# SCH_NFC-Hacker-Card_2024-08-06.net
KiCad netlist of a schematic drawn in EasyEDA
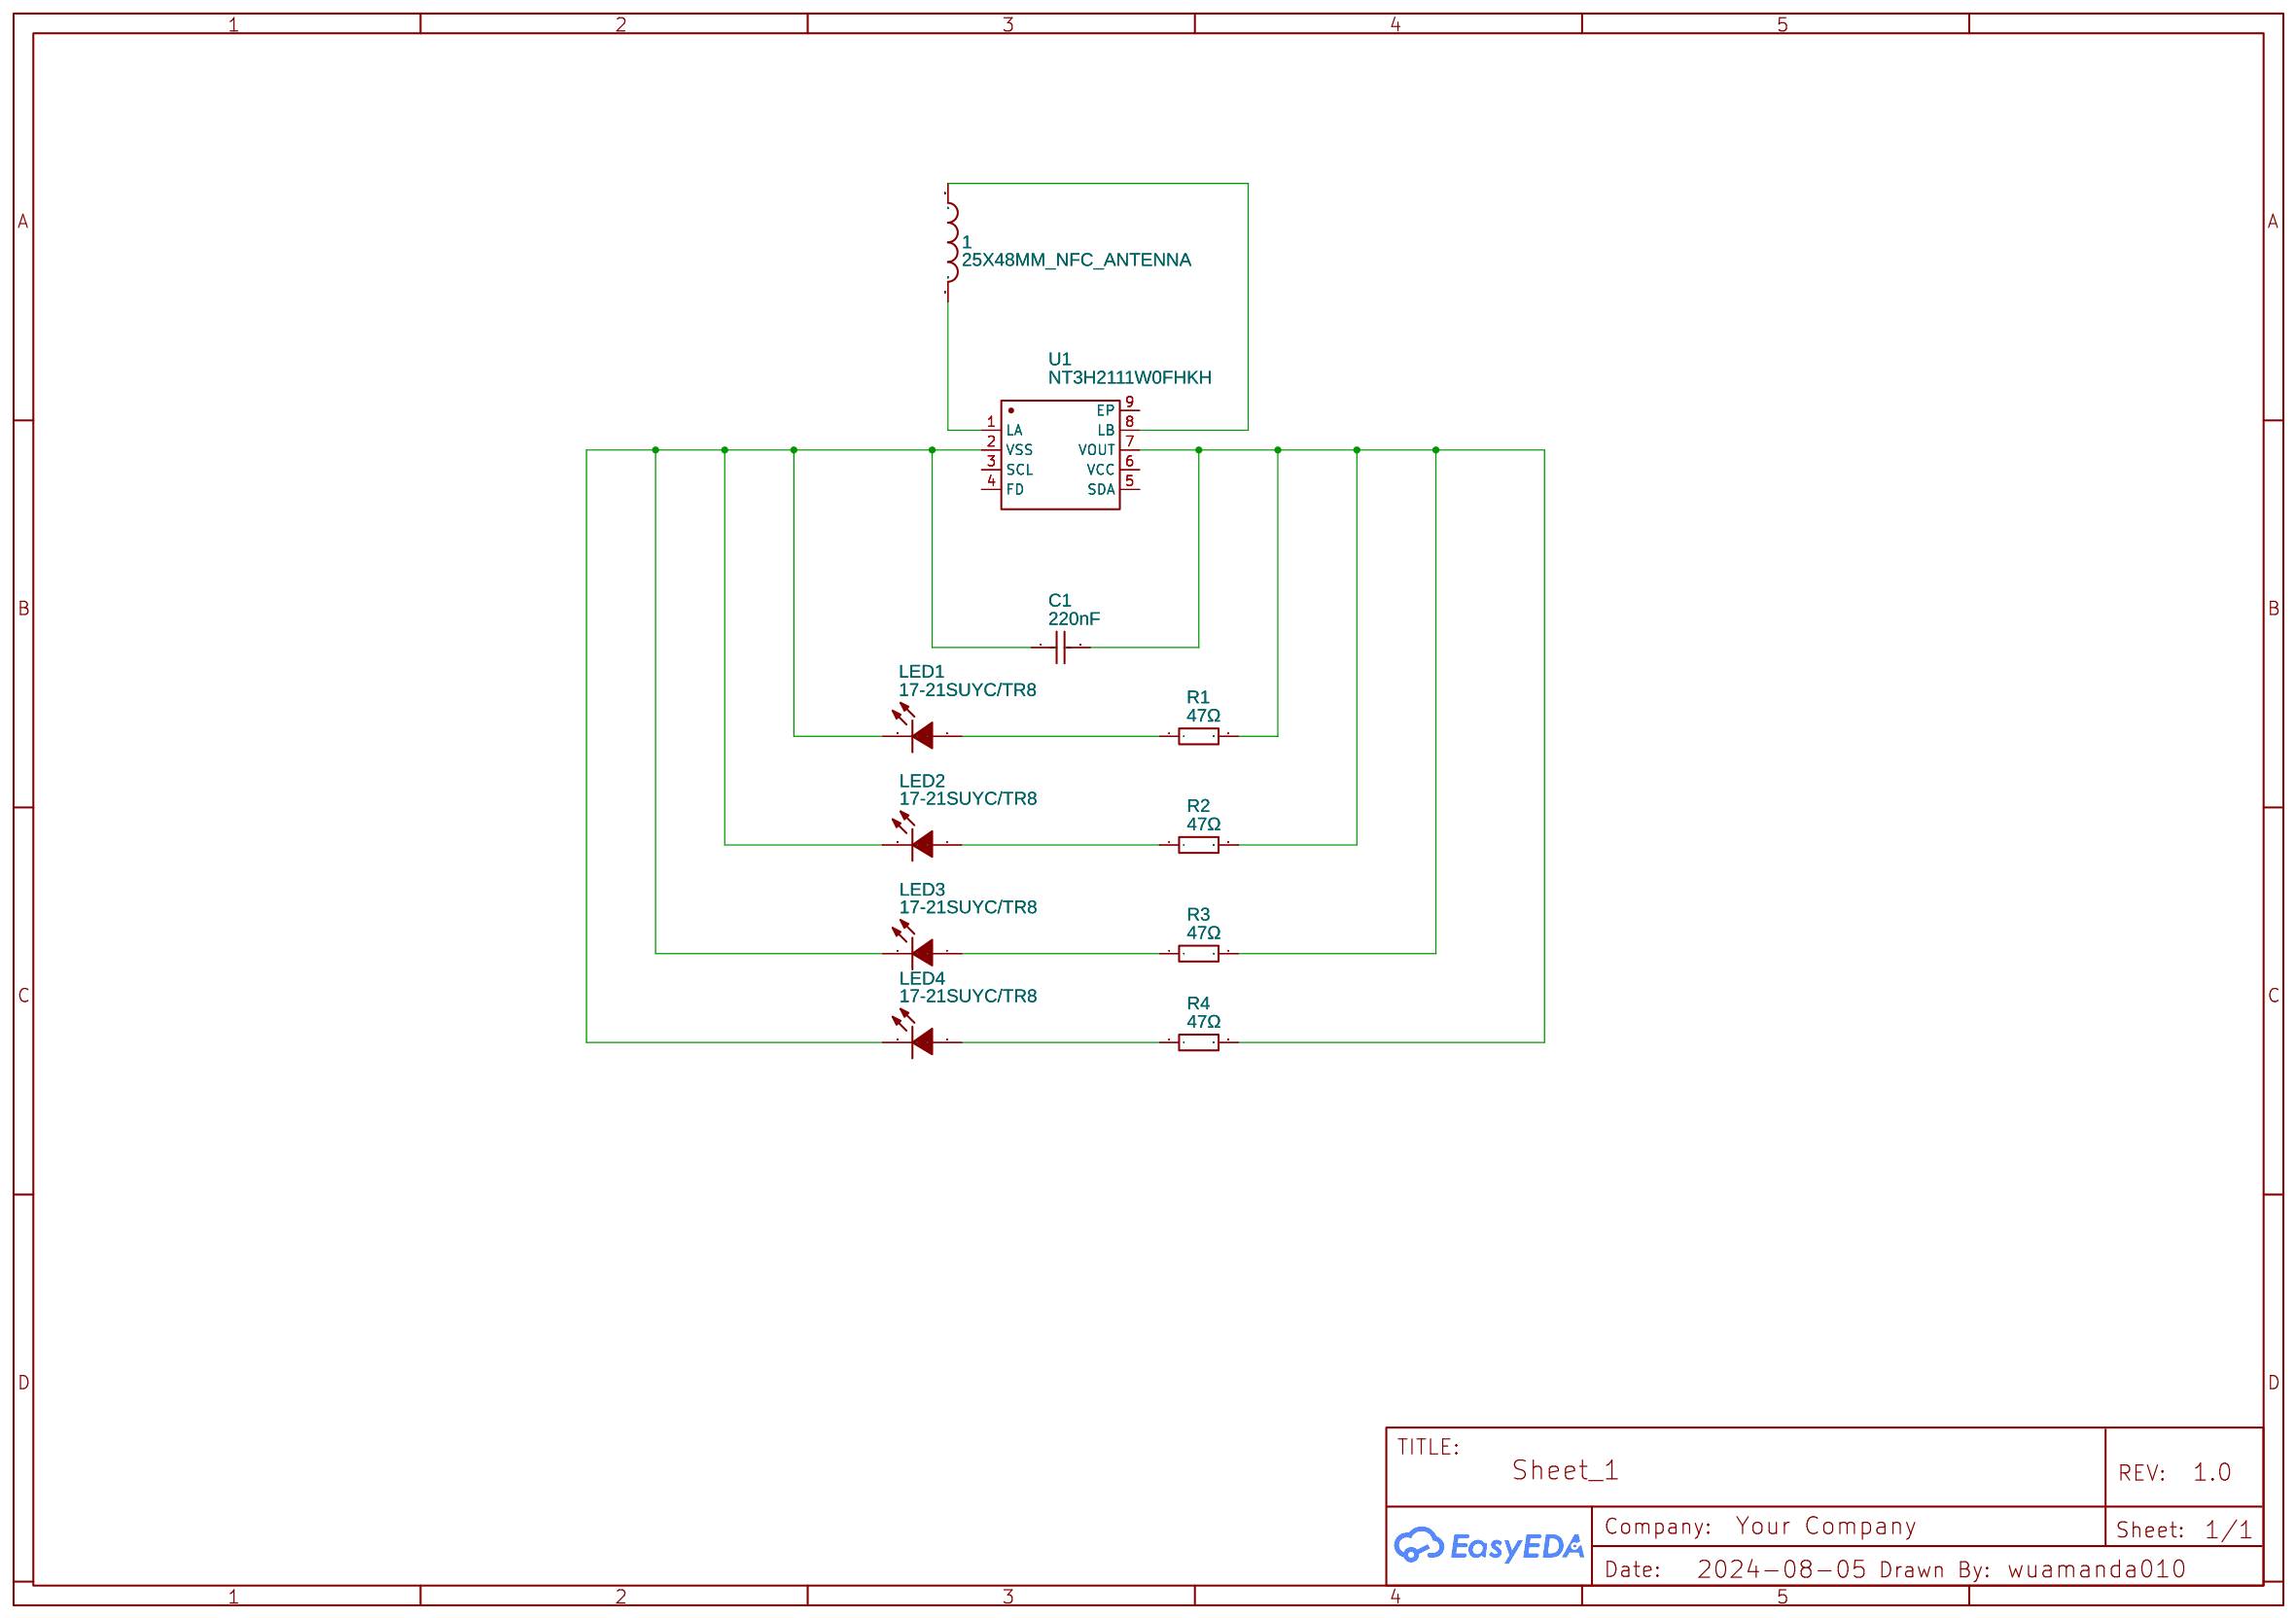
[diagram p0: schematic sheet]

(export (version "E")
  (design (tool "Eeschema 10.0.6"))
  (components
    (comp (ref "1") (value "25X48MM_NFC_ANTENNA") (libsource (lib "") (part "25X48MM_NFC_ANTENNA")))
    (comp (ref "C1")
      (value "220nF")
      (fields
        (field (name "Manufacturer Part") "CL10B224KA8NNNC")
        (field (name "Manufacturer") "SAMSUNG(三星)")
      )
      (libsource (lib "") (part "CL10B224KA8NNNC"))
    )
    (comp (ref "LED1")
      (value "17-21SUYC/TR8")
      (fields (field (name "Manufacturer Part") "KT-0805黄灯") (field (name "Manufacturer") "KENTO"))
      (libsource (lib "") (part "17-21SUYC/TR8"))
    )
    (comp (ref "LED2")
      (value "17-21SUYC/TR8")
      (fields (field (name "Manufacturer Part") "KT-0805黄灯") (field (name "Manufacturer") "KENTO"))
      (libsource (lib "") (part "17-21SUYC/TR8"))
    )
    (comp (ref "LED3")
      (value "17-21SUYC/TR8")
      (fields (field (name "Manufacturer Part") "KT-0805黄灯") (field (name "Manufacturer") "KENTO"))
      (libsource (lib "") (part "17-21SUYC/TR8"))
    )
    (comp (ref "LED4")
      (value "17-21SUYC/TR8")
      (fields (field (name "Manufacturer Part") "KT-0805黄灯") (field (name "Manufacturer") "KENTO"))
      (libsource (lib "") (part "17-21SUYC/TR8"))
    )
    (comp (ref "R1")
      (value "47Ω")
      (fields
        (field (name "Manufacturer Part") "0603WAF470JT5E")
        (field (name "Manufacturer") "UNI-ROYAL(厚声)")
      )
      (libsource (lib "") (part "0603WAF470JT5E"))
    )
    (comp (ref "R2")
      (value "47Ω")
      (fields
        (field (name "Manufacturer Part") "0603WAF470JT5E")
        (field (name "Manufacturer") "UNI-ROYAL(厚声)")
      )
      (libsource (lib "") (part "0603WAF470JT5E"))
    )
    (comp (ref "R3")
      (value "47Ω")
      (fields
        (field (name "Manufacturer Part") "0603WAF470JT5E")
        (field (name "Manufacturer") "UNI-ROYAL(厚声)")
      )
      (libsource (lib "") (part "0603WAF470JT5E"))
    )
    (comp (ref "R4")
      (value "47Ω")
      (fields
        (field (name "Manufacturer Part") "0603WAF470JT5E")
        (field (name "Manufacturer") "UNI-ROYAL(厚声)")
      )
      (libsource (lib "") (part "0603WAF470JT5E"))
    )
    (comp (ref "U1")
      (value "NT3H2111W0FHKH")
      (fields (field (name "Manufacturer") "NXP(恩智浦)"))
      (libsource (lib "") (part "NT3H2111W0FHKH"))
    )
  )
  (nets
    (net (code "1") (name "Net-(LED1-+)") (class "Default")
      (node (ref "LED1") (pin "1") (pinfunction "+_1") (pintype "unspecified"))
      (node (ref "R1") (pin "1") (pinfunction "1_1") (pintype "input"))
    )
    (net (code "2") (name "Net-(LED1--)") (class "Default")
      (node (ref "C1") (pin "1") (pinfunction "1_1") (pintype "input"))
      (node (ref "LED1") (pin "2") (pinfunction "-_2") (pintype "unspecified"))
      (node (ref "LED2") (pin "2") (pinfunction "-_2") (pintype "unspecified"))
      (node (ref "LED3") (pin "2") (pinfunction "-_2") (pintype "unspecified"))
      (node (ref "LED4") (pin "2") (pinfunction "-_2") (pintype "unspecified"))
      (node (ref "U1") (pin "2") (pinfunction "VSS_2") (pintype "unspecified"))
    )
    (net (code "3") (name "Net-(LED2-+)") (class "Default")
      (node (ref "LED2") (pin "1") (pinfunction "+_1") (pintype "unspecified"))
      (node (ref "R2") (pin "1") (pinfunction "1_1") (pintype "input"))
    )
    (net (code "4") (name "Net-(LED3-+)") (class "Default")
      (node (ref "LED3") (pin "1") (pinfunction "+_1") (pintype "unspecified"))
      (node (ref "R3") (pin "1") (pinfunction "1_1") (pintype "input"))
    )
    (net (code "5") (name "Net-(LED4-+)") (class "Default")
      (node (ref "LED4") (pin "1") (pinfunction "+_1") (pintype "unspecified"))
      (node (ref "R4") (pin "1") (pinfunction "1_1") (pintype "input"))
    )
    (net (code "6") (name "Net-(U1-LA)") (class "Default")
      (node (ref "1") (pin "P$2") (pinfunction "P$2_P$2") (pintype "bidirectional"))
      (node (ref "U1") (pin "1") (pinfunction "LA_1") (pintype "unspecified"))
    )
    (net (code "7") (name "Net-(U1-LB)") (class "Default")
      (node (ref "1") (pin "P$1") (pinfunction "P$1_P$1") (pintype "bidirectional"))
      (node (ref "U1") (pin "8") (pinfunction "LB_8") (pintype "unspecified"))
    )
    (net (code "8") (name "Net-(U1-VOUT)") (class "Default")
      (node (ref "C1") (pin "2") (pinfunction "2_2") (pintype "input"))
      (node (ref "R1") (pin "2") (pinfunction "2_2") (pintype "input"))
      (node (ref "R2") (pin "2") (pinfunction "2_2") (pintype "input"))
      (node (ref "R3") (pin "2") (pinfunction "2_2") (pintype "input"))
      (node (ref "R4") (pin "2") (pinfunction "2_2") (pintype "input"))
      (node (ref "U1") (pin "7") (pinfunction "VOUT_7") (pintype "unspecified"))
    )
    (net (code "9") (name "unconnected-(U1-EP-Pad9)") (class "Default")
      (node (ref "U1") (pin "9") (pinfunction "EP_9") (pintype "unspecified"))
    )
    (net (code "10") (name "unconnected-(U1-FD-Pad4)") (class "Default")
      (node (ref "U1") (pin "4") (pinfunction "FD_4") (pintype "unspecified"))
    )
    (net (code "11") (name "unconnected-(U1-SCL-Pad3)") (class "Default")
      (node (ref "U1") (pin "3") (pinfunction "SCL_3") (pintype "unspecified"))
    )
    (net (code "12") (name "unconnected-(U1-SDA-Pad5)") (class "Default")
      (node (ref "U1") (pin "5") (pinfunction "SDA_5") (pintype "unspecified"))
    )
    (net (code "13") (name "unconnected-(U1-VCC-Pad6)") (class "Default")
      (node (ref "U1") (pin "6") (pinfunction "VCC_6") (pintype "unspecified"))
    )
  )
)
